# motor.net
KiCad netlist of a schematic drawn in Altium Designer
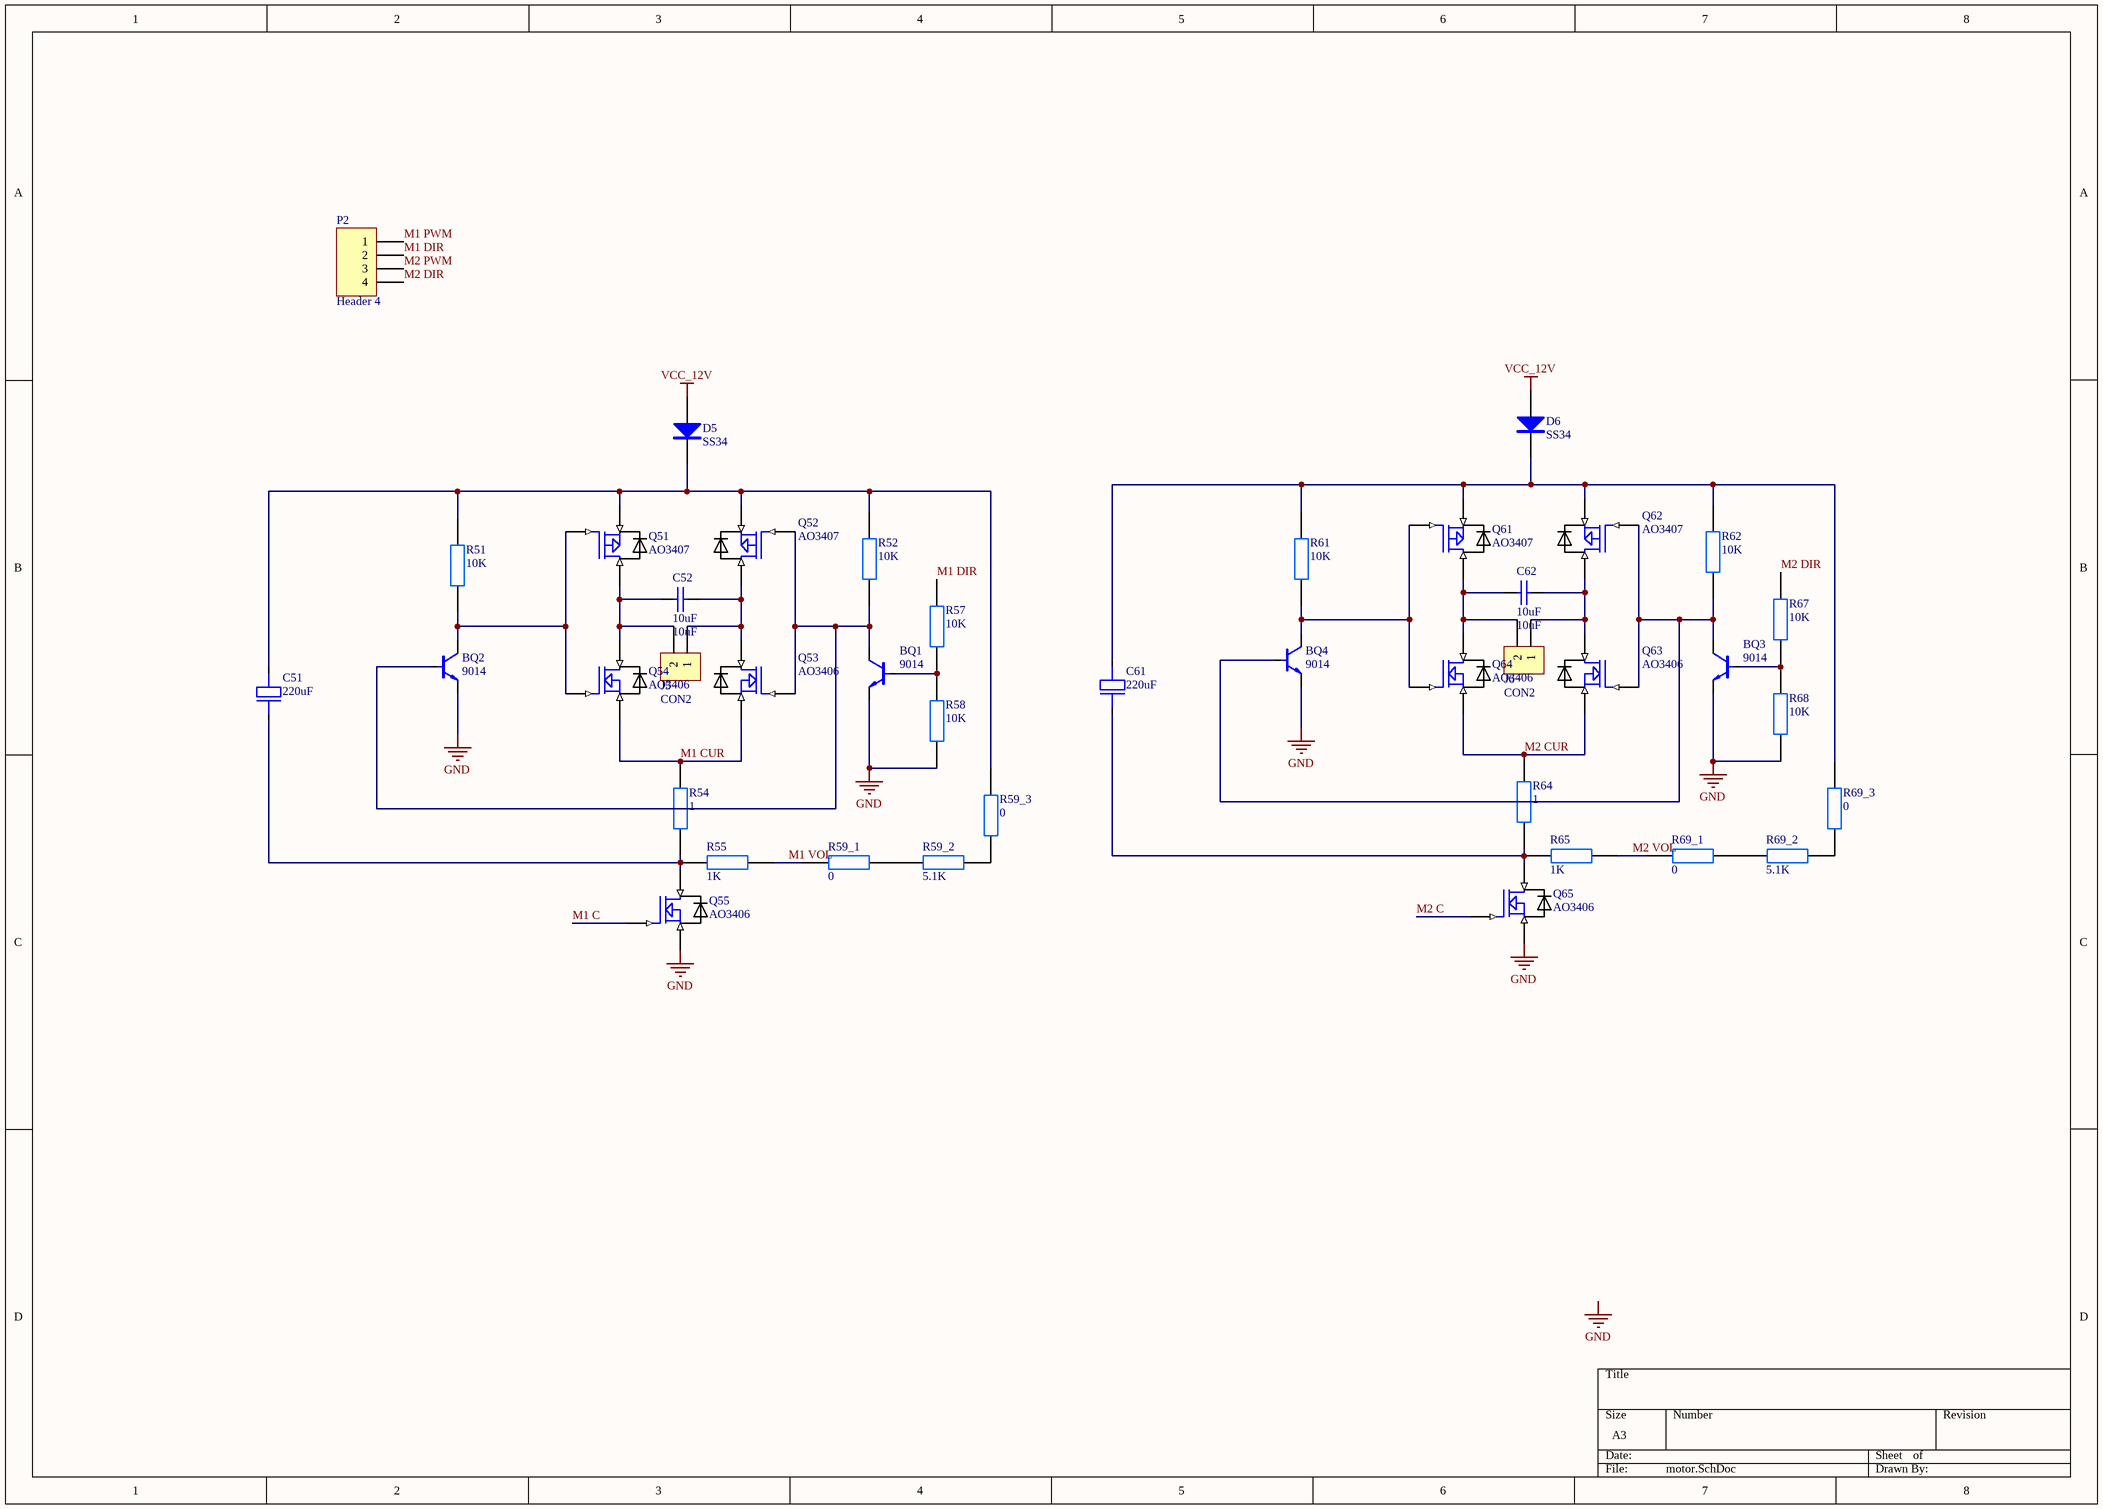
[diagram p0: motor.SchDoc]

(export (version "E")
  (design (tool "Eeschema 10.0.6"))
  (components
    (comp (ref "BQ1")
      (value "9014")
      (footprint "SOT-23")
      (description "transistor")
      (libsource (lib "common") (part "9014"))
    )
    (comp (ref "BQ2")
      (value "9014")
      (footprint "SOT-23")
      (description "transistor")
      (libsource (lib "common") (part "9014"))
    )
    (comp (ref "BQ3")
      (value "9014")
      (footprint "SOT-23")
      (description "transistor")
      (libsource (lib "common") (part "9014"))
    )
    (comp (ref "BQ4")
      (value "9014")
      (footprint "SOT-23")
      (description "transistor")
      (libsource (lib "common") (part "9014"))
    )
    (comp (ref "C51")
      (value "220uF")
      (footprint "SMD-EC-F10")
      (libsource (lib "common") (part "Electrolytic CAP"))
    )
    (comp (ref "C52")
      (value "10uF")
      (footprint "0805 CAP")
      (fields (field (name "ALTIUM_VALUE") "10uF"))
      (libsource (lib "common") (part "CAP"))
    )
    (comp (ref "C61")
      (value "220uF")
      (footprint "SMD-EC-F10")
      (libsource (lib "common") (part "Electrolytic CAP"))
    )
    (comp (ref "C62")
      (value "10uF")
      (footprint "0805 CAP")
      (fields (field (name "ALTIUM_VALUE") "10uF"))
      (libsource (lib "common") (part "CAP"))
    )
    (comp (ref "D5")
      (value "SS34")
      (footprint "SMA")
      (description "Diode")
      (libsource (lib "common") (part "SS14"))
    )
    (comp (ref "D6")
      (value "SS34")
      (footprint "SMA")
      (description "Diode")
      (libsource (lib "common") (part "SS14"))
    )
    (comp (ref "J5") (value "CON2") (footprint "con2") (libsource (lib "common") (part "CON2")))
    (comp (ref "J6") (value "CON2") (footprint "con2") (libsource (lib "common") (part "CON2")))
    (comp (ref "P2")
      (value "Header 4")
      (footprint "HDR1X4")
      (description "Header, 4-Pin")
      (fields (field (name "PUBLISHER") "Altium Limited"))
      (libsource (lib "Miscellaneous Connectors") (part "Header 4"))
    )
    (comp (ref "Q51") (value "AO3407") (footprint "sot-23") (libsource (lib "common") (part "AO3407")))
    (comp (ref "Q52") (value "AO3407") (footprint "sot-23") (libsource (lib "common") (part "AO3407")))
    (comp (ref "Q53") (value "AO3406") (footprint "sot-23") (libsource (lib "common") (part "AO3406")))
    (comp (ref "Q54") (value "AO3406") (footprint "sot-23") (libsource (lib "common") (part "AO3406")))
    (comp (ref "Q55") (value "AO3406") (footprint "sot-23") (libsource (lib "common") (part "AO3406")))
    (comp (ref "Q61") (value "AO3407") (footprint "sot-23") (libsource (lib "common") (part "AO3407")))
    (comp (ref "Q62") (value "AO3407") (footprint "sot-23") (libsource (lib "common") (part "AO3407")))
    (comp (ref "Q63") (value "AO3406") (footprint "sot-23") (libsource (lib "common") (part "AO3406")))
    (comp (ref "Q64") (value "AO3406") (footprint "sot-23") (libsource (lib "common") (part "AO3406")))
    (comp (ref "Q65") (value "AO3406") (footprint "sot-23") (libsource (lib "common") (part "AO3406")))
    (comp (ref "R51")
      (value "10K")
      (footprint "0805")
      (description "RES")
      (libsource (lib "common") (part "RES"))
    )
    (comp (ref "R52")
      (value "10K")
      (footprint "0805")
      (description "RES")
      (libsource (lib "common") (part "RES"))
    )
    (comp (ref "R54")
      (value "1")
      (footprint "2512")
      (description "RES")
      (libsource (lib "common") (part "RES"))
    )
    (comp (ref "R55")
      (value "1K")
      (footprint "0805")
      (description "RES")
      (libsource (lib "common") (part "RES"))
    )
    (comp (ref "R57")
      (value "10K")
      (footprint "0805")
      (description "RES")
      (libsource (lib "common") (part "RES"))
    )
    (comp (ref "R58")
      (value "10K")
      (footprint "0805")
      (description "RES")
      (libsource (lib "common") (part "RES"))
    )
    (comp (ref "R59_1")
      (value "0")
      (footprint "0805")
      (description "RES")
      (libsource (lib "common") (part "RES"))
    )
    (comp (ref "R59_2")
      (value "5.1K")
      (footprint "0805")
      (description "RES")
      (libsource (lib "common") (part "RES"))
    )
    (comp (ref "R59_3")
      (value "0")
      (footprint "0805")
      (description "RES")
      (libsource (lib "common") (part "RES"))
    )
    (comp (ref "R61")
      (value "10K")
      (footprint "0805")
      (description "RES")
      (libsource (lib "common") (part "RES"))
    )
    (comp (ref "R62")
      (value "10K")
      (footprint "0805")
      (description "RES")
      (libsource (lib "common") (part "RES"))
    )
    (comp (ref "R64")
      (value "1")
      (footprint "2512")
      (description "RES")
      (libsource (lib "common") (part "RES"))
    )
    (comp (ref "R65")
      (value "1K")
      (footprint "0805")
      (description "RES")
      (libsource (lib "common") (part "RES"))
    )
    (comp (ref "R67")
      (value "10K")
      (footprint "0805")
      (description "RES")
      (libsource (lib "common") (part "RES"))
    )
    (comp (ref "R68")
      (value "10K")
      (footprint "0805")
      (description "RES")
      (libsource (lib "common") (part "RES"))
    )
    (comp (ref "R69_1")
      (value "0")
      (footprint "0805")
      (description "RES")
      (libsource (lib "common") (part "RES"))
    )
    (comp (ref "R69_2")
      (value "5.1K")
      (footprint "0805")
      (description "RES")
      (libsource (lib "common") (part "RES"))
    )
    (comp (ref "R69_3")
      (value "0")
      (footprint "0805")
      (description "RES")
      (libsource (lib "common") (part "RES"))
    )
  )
  (nets
    (net (code "1") (name "/M1 C") (class "Default")
      (node (ref "Q55") (pin "1") (pinfunction "G_1") (pintype "input"))
    )
    (net (code "2") (name "/M1 CUR") (class "Default")
      (node (ref "Q53") (pin "3") (pinfunction "S_3") (pintype "input"))
      (node (ref "Q54") (pin "3") (pinfunction "S_3") (pintype "input"))
      (node (ref "R54") (pin "2") (pinfunction "2_2") (pintype "passive"))
    )
    (net (code "3") (name "/M1 DIR") (class "Default")
      (node (ref "P2") (pin "2") (pinfunction "2_2") (pintype "passive"))
      (node (ref "R57") (pin "2") (pinfunction "2_2") (pintype "passive"))
    )
    (net (code "4") (name "/M1 PWM") (class "Default")
      (node (ref "P2") (pin "1") (pinfunction "1_1") (pintype "passive"))
    )
    (net (code "5") (name "/M1 VOL") (class "Default")
      (node (ref "R55") (pin "2") (pinfunction "2_2") (pintype "passive"))
      (node (ref "R59_1") (pin "2") (pinfunction "2_2") (pintype "passive"))
    )
    (net (code "6") (name "/M2 C") (class "Default")
      (node (ref "Q65") (pin "1") (pinfunction "G_1") (pintype "input"))
    )
    (net (code "7") (name "/M2 CUR") (class "Default")
      (node (ref "Q63") (pin "3") (pinfunction "S_3") (pintype "input"))
      (node (ref "Q64") (pin "3") (pinfunction "S_3") (pintype "input"))
      (node (ref "R64") (pin "2") (pinfunction "2_2") (pintype "passive"))
    )
    (net (code "8") (name "/M2 DIR") (class "Default")
      (node (ref "P2") (pin "4") (pinfunction "4_4") (pintype "passive"))
      (node (ref "R67") (pin "2") (pinfunction "2_2") (pintype "passive"))
    )
    (net (code "9") (name "/M2 PWM") (class "Default")
      (node (ref "P2") (pin "3") (pinfunction "3_3") (pintype "passive"))
    )
    (net (code "10") (name "/M2 VOL") (class "Default")
      (node (ref "R65") (pin "2") (pinfunction "2_2") (pintype "passive"))
      (node (ref "R69_1") (pin "2") (pinfunction "2_2") (pintype "passive"))
    )
    (net (code "11") (name "GND") (class "Default")
      (node (ref "BQ1") (pin "e") (pinfunction "e_e") (pintype "passive"))
      (node (ref "BQ2") (pin "e") (pinfunction "e_e") (pintype "passive"))
      (node (ref "BQ3") (pin "e") (pinfunction "e_e") (pintype "passive"))
      (node (ref "BQ4") (pin "e") (pinfunction "e_e") (pintype "passive"))
      (node (ref "Q55") (pin "3") (pinfunction "S_3") (pintype "input"))
      (node (ref "Q65") (pin "3") (pinfunction "S_3") (pintype "input"))
      (node (ref "R58") (pin "1") (pinfunction "1_1") (pintype "passive"))
      (node (ref "R68") (pin "1") (pinfunction "1_1") (pintype "passive"))
    )
    (net (code "12") (name "Net-(BQ1-Padb)") (class "Default")
      (node (ref "BQ1") (pin "b") (pinfunction "b_b") (pintype "passive"))
      (node (ref "R57") (pin "1") (pinfunction "1_1") (pintype "passive"))
      (node (ref "R58") (pin "2") (pinfunction "2_2") (pintype "passive"))
    )
    (net (code "13") (name "Net-(BQ3-Padb)") (class "Default")
      (node (ref "BQ3") (pin "b") (pinfunction "b_b") (pintype "passive"))
      (node (ref "R67") (pin "1") (pinfunction "1_1") (pintype "passive"))
      (node (ref "R68") (pin "2") (pinfunction "2_2") (pintype "passive"))
    )
    (net (code "14") (name "Net-(D5-K)") (class "Default")
      (node (ref "C51") (pin "1") (pinfunction "1_1") (pintype "passive"))
      (node (ref "D5") (pin "2") (pinfunction "K_2") (pintype "passive"))
      (node (ref "Q51") (pin "3") (pinfunction "S_3") (pintype "input"))
      (node (ref "Q52") (pin "3") (pinfunction "S_3") (pintype "input"))
      (node (ref "R51") (pin "2") (pinfunction "2_2") (pintype "passive"))
      (node (ref "R52") (pin "2") (pinfunction "2_2") (pintype "passive"))
      (node (ref "R59_3") (pin "2") (pinfunction "2_2") (pintype "passive"))
    )
    (net (code "15") (name "Net-(D6-K)") (class "Default")
      (node (ref "C61") (pin "1") (pinfunction "1_1") (pintype "passive"))
      (node (ref "D6") (pin "2") (pinfunction "K_2") (pintype "passive"))
      (node (ref "Q61") (pin "3") (pinfunction "S_3") (pintype "input"))
      (node (ref "Q62") (pin "3") (pinfunction "S_3") (pintype "input"))
      (node (ref "R61") (pin "2") (pinfunction "2_2") (pintype "passive"))
      (node (ref "R62") (pin "2") (pinfunction "2_2") (pintype "passive"))
      (node (ref "R69_3") (pin "2") (pinfunction "2_2") (pintype "passive"))
    )
    (net (code "16") (name "Net-(Q51-D)") (class "Default")
      (node (ref "C52") (pin "1") (pinfunction "1_1") (pintype "passive"))
      (node (ref "J5") (pin "2") (pinfunction "2_2") (pintype "passive"))
      (node (ref "Q51") (pin "2") (pinfunction "D_2") (pintype "input"))
      (node (ref "Q54") (pin "2") (pinfunction "D_2") (pintype "input"))
    )
    (net (code "17") (name "Net-(Q51-G)") (class "Default")
      (node (ref "BQ2") (pin "c") (pinfunction "c_c") (pintype "passive"))
      (node (ref "Q51") (pin "1") (pinfunction "G_1") (pintype "input"))
      (node (ref "Q54") (pin "1") (pinfunction "G_1") (pintype "input"))
      (node (ref "R51") (pin "1") (pinfunction "1_1") (pintype "passive"))
    )
    (net (code "18") (name "Net-(Q52-D)") (class "Default")
      (node (ref "C52") (pin "2") (pinfunction "2_2") (pintype "passive"))
      (node (ref "J5") (pin "1") (pinfunction "1_1") (pintype "passive"))
      (node (ref "Q52") (pin "2") (pinfunction "D_2") (pintype "input"))
      (node (ref "Q53") (pin "2") (pinfunction "D_2") (pintype "input"))
    )
    (net (code "19") (name "Net-(Q52-G)") (class "Default")
      (node (ref "BQ1") (pin "c") (pinfunction "c_c") (pintype "passive"))
      (node (ref "BQ2") (pin "b") (pinfunction "b_b") (pintype "passive"))
      (node (ref "Q52") (pin "1") (pinfunction "G_1") (pintype "input"))
      (node (ref "Q53") (pin "1") (pinfunction "G_1") (pintype "input"))
      (node (ref "R52") (pin "1") (pinfunction "1_1") (pintype "passive"))
    )
    (net (code "20") (name "Net-(Q55-D)") (class "Default")
      (node (ref "C51") (pin "2") (pinfunction "2_2") (pintype "passive"))
      (node (ref "Q55") (pin "2") (pinfunction "D_2") (pintype "input"))
      (node (ref "R54") (pin "1") (pinfunction "1_1") (pintype "passive"))
      (node (ref "R55") (pin "1") (pinfunction "1_1") (pintype "passive"))
    )
    (net (code "21") (name "Net-(Q61-D)") (class "Default")
      (node (ref "C62") (pin "1") (pinfunction "1_1") (pintype "passive"))
      (node (ref "J6") (pin "2") (pinfunction "2_2") (pintype "passive"))
      (node (ref "Q61") (pin "2") (pinfunction "D_2") (pintype "input"))
      (node (ref "Q64") (pin "2") (pinfunction "D_2") (pintype "input"))
    )
    (net (code "22") (name "Net-(Q61-G)") (class "Default")
      (node (ref "BQ4") (pin "c") (pinfunction "c_c") (pintype "passive"))
      (node (ref "Q61") (pin "1") (pinfunction "G_1") (pintype "input"))
      (node (ref "Q64") (pin "1") (pinfunction "G_1") (pintype "input"))
      (node (ref "R61") (pin "1") (pinfunction "1_1") (pintype "passive"))
    )
    (net (code "23") (name "Net-(Q62-D)") (class "Default")
      (node (ref "C62") (pin "2") (pinfunction "2_2") (pintype "passive"))
      (node (ref "J6") (pin "1") (pinfunction "1_1") (pintype "passive"))
      (node (ref "Q62") (pin "2") (pinfunction "D_2") (pintype "input"))
      (node (ref "Q63") (pin "2") (pinfunction "D_2") (pintype "input"))
    )
    (net (code "24") (name "Net-(Q62-G)") (class "Default")
      (node (ref "BQ3") (pin "c") (pinfunction "c_c") (pintype "passive"))
      (node (ref "BQ4") (pin "b") (pinfunction "b_b") (pintype "passive"))
      (node (ref "Q62") (pin "1") (pinfunction "G_1") (pintype "input"))
      (node (ref "Q63") (pin "1") (pinfunction "G_1") (pintype "input"))
      (node (ref "R62") (pin "1") (pinfunction "1_1") (pintype "passive"))
    )
    (net (code "25") (name "Net-(Q65-D)") (class "Default")
      (node (ref "C61") (pin "2") (pinfunction "2_2") (pintype "passive"))
      (node (ref "Q65") (pin "2") (pinfunction "D_2") (pintype "input"))
      (node (ref "R64") (pin "1") (pinfunction "1_1") (pintype "passive"))
      (node (ref "R65") (pin "1") (pinfunction "1_1") (pintype "passive"))
    )
    (net (code "26") (name "Net-(R59_1-Pad1)") (class "Default")
      (node (ref "R59_1") (pin "1") (pinfunction "1_1") (pintype "passive"))
      (node (ref "R59_2") (pin "1") (pinfunction "1_1") (pintype "passive"))
    )
    (net (code "27") (name "Net-(R59_2-Pad2)") (class "Default")
      (node (ref "R59_2") (pin "2") (pinfunction "2_2") (pintype "passive"))
      (node (ref "R59_3") (pin "1") (pinfunction "1_1") (pintype "passive"))
    )
    (net (code "28") (name "Net-(R69_1-Pad1)") (class "Default")
      (node (ref "R69_1") (pin "1") (pinfunction "1_1") (pintype "passive"))
      (node (ref "R69_2") (pin "1") (pinfunction "1_1") (pintype "passive"))
    )
    (net (code "29") (name "Net-(R69_2-Pad2)") (class "Default")
      (node (ref "R69_2") (pin "2") (pinfunction "2_2") (pintype "passive"))
      (node (ref "R69_3") (pin "1") (pinfunction "1_1") (pintype "passive"))
    )
    (net (code "30") (name "VCC_12V") (class "Default")
      (node (ref "D5") (pin "1") (pinfunction "A_1") (pintype "passive"))
      (node (ref "D6") (pin "1") (pinfunction "A_1") (pintype "passive"))
    )
  )
)
